# LR-CR.net
KiCad netlist of a schematic drawn in EAGLE
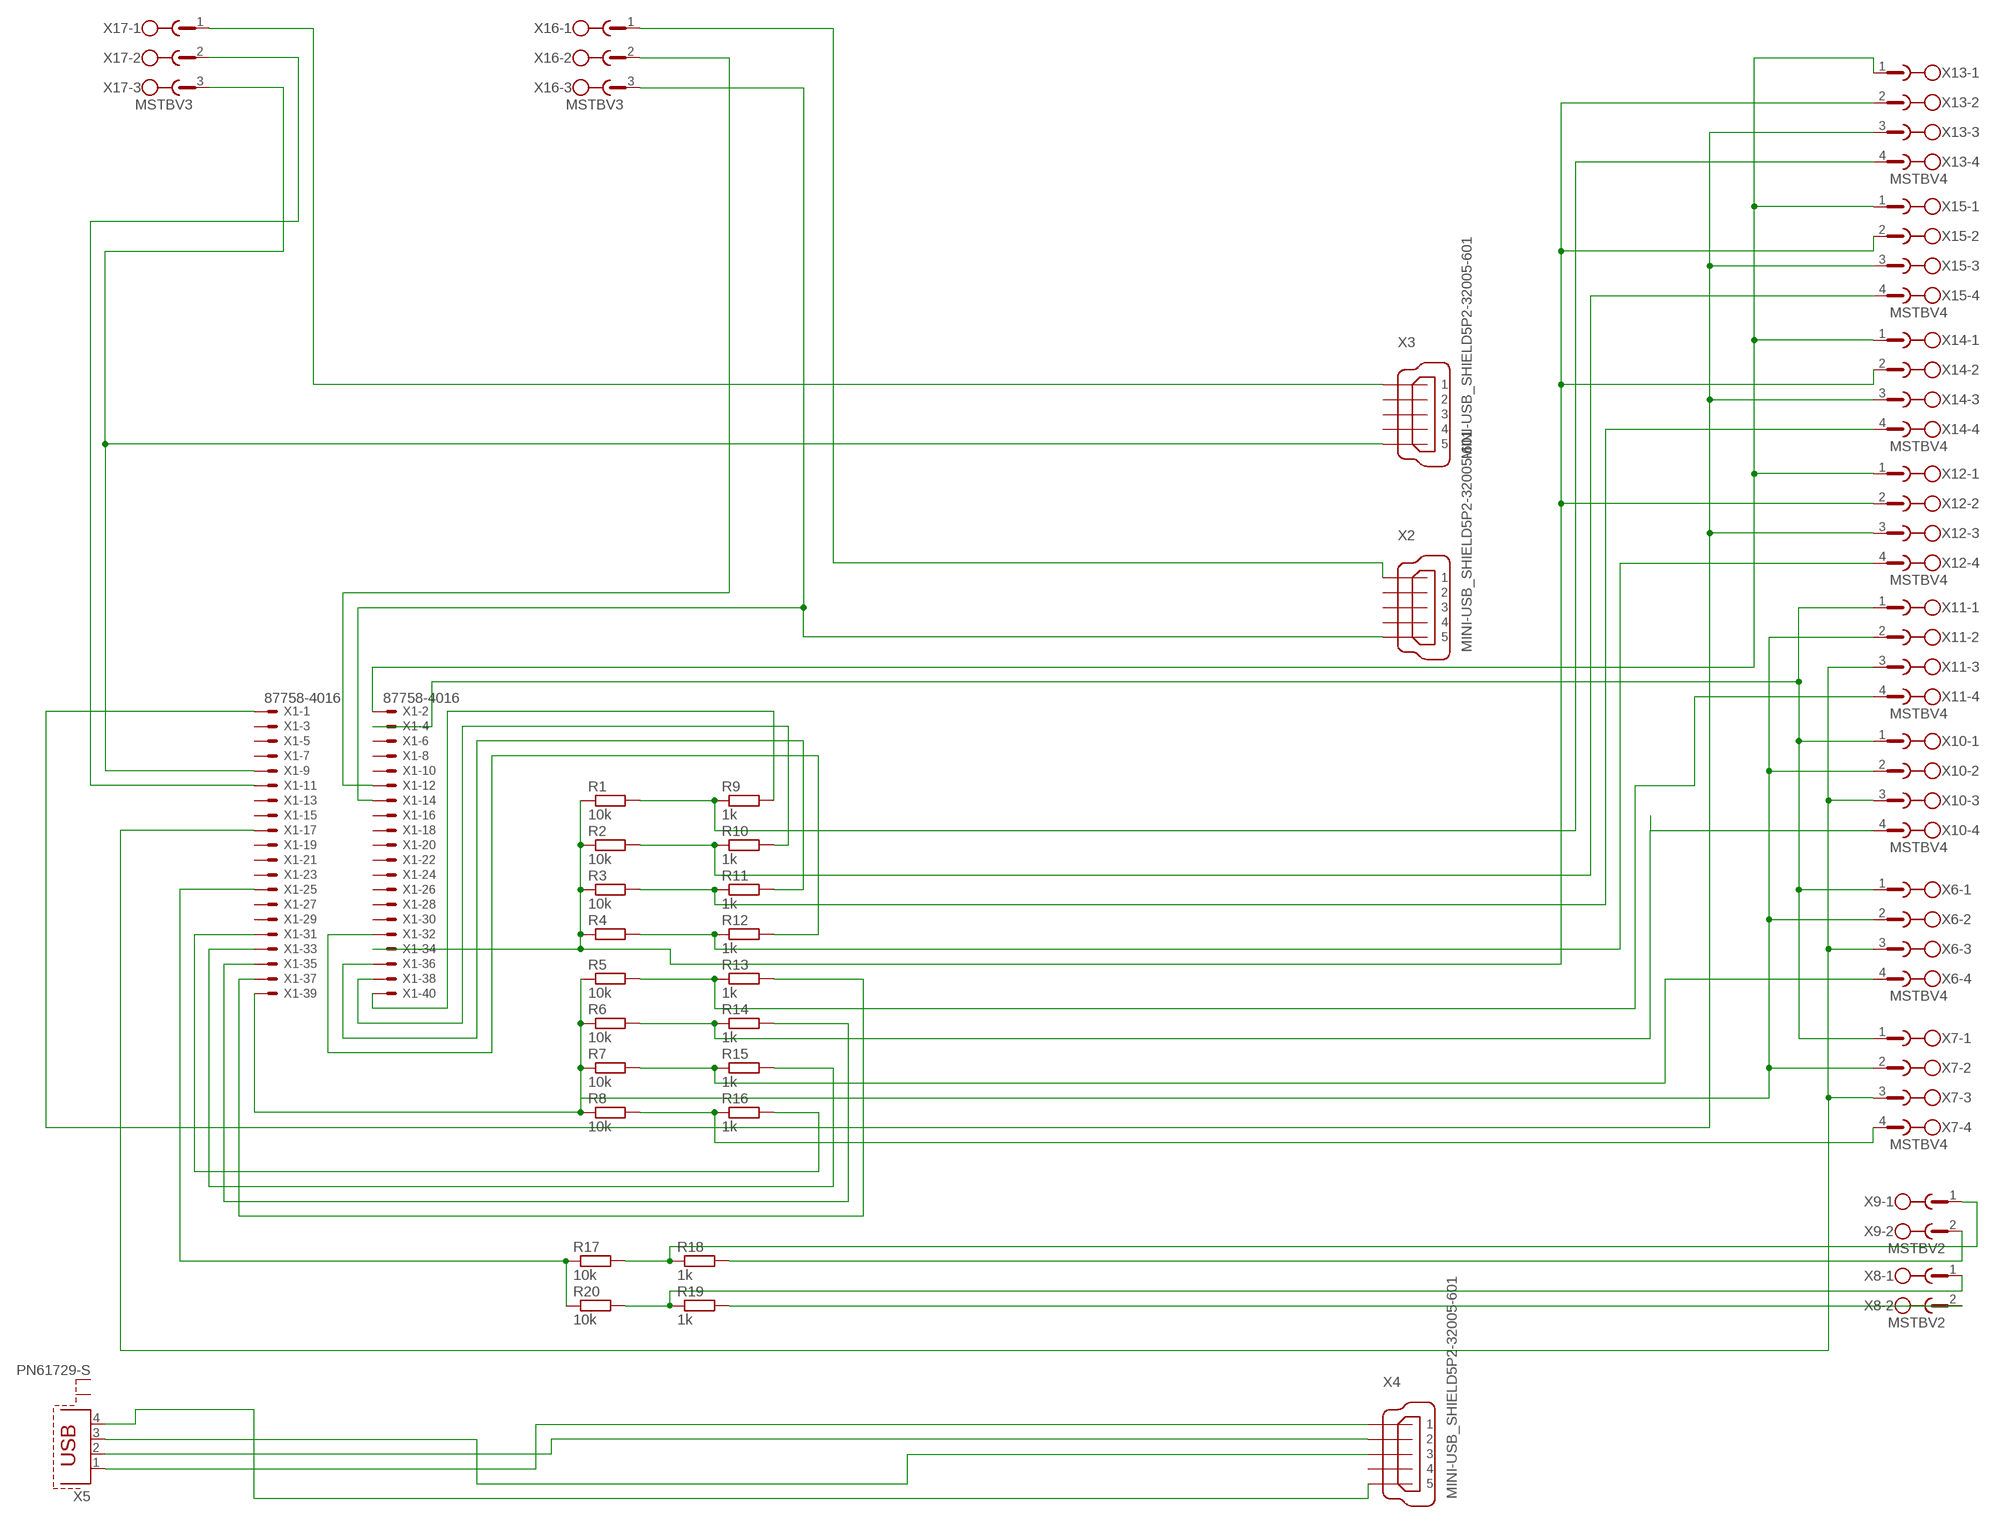
[diagram p0: schematic, sheet 1]

(export (version "E")
  (design (tool "Eeschema 10.0.6"))
  (components
    (comp (ref "R1")
      (value "10k")
      (footprint "eagle-import:0411_15")
      (libsource (lib "eagle-import") (part "R-EU_0411/15"))
    )
    (comp (ref "R2")
      (value "10k")
      (footprint "eagle-import:0411_15")
      (libsource (lib "eagle-import") (part "R-EU_0411/15"))
    )
    (comp (ref "R3")
      (value "10k")
      (footprint "eagle-import:0411_15")
      (libsource (lib "eagle-import") (part "R-EU_0411/15"))
    )
    (comp (ref "R4")
      (value "R-EU_0411/15")
      (footprint "eagle-import:0411_15")
      (libsource (lib "eagle-import") (part "R-EU_0411/15"))
    )
    (comp (ref "R5")
      (value "10k")
      (footprint "eagle-import:0411_15")
      (libsource (lib "eagle-import") (part "R-EU_0411/15"))
    )
    (comp (ref "R6")
      (value "10k")
      (footprint "eagle-import:0411_15")
      (libsource (lib "eagle-import") (part "R-EU_0411/15"))
    )
    (comp (ref "R7")
      (value "10k")
      (footprint "eagle-import:0411_15")
      (libsource (lib "eagle-import") (part "R-EU_0411/15"))
    )
    (comp (ref "R8")
      (value "10k")
      (footprint "eagle-import:0411_15")
      (libsource (lib "eagle-import") (part "R-EU_0411/15"))
    )
    (comp (ref "R9")
      (value "1k")
      (footprint "eagle-import:0411_15")
      (libsource (lib "eagle-import") (part "R-EU_0411/15"))
    )
    (comp (ref "R10")
      (value "1k")
      (footprint "eagle-import:0411_15")
      (libsource (lib "eagle-import") (part "R-EU_0411/15"))
    )
    (comp (ref "R11")
      (value "1k")
      (footprint "eagle-import:0411_15")
      (libsource (lib "eagle-import") (part "R-EU_0411/15"))
    )
    (comp (ref "R12")
      (value "1k")
      (footprint "eagle-import:0411_15")
      (libsource (lib "eagle-import") (part "R-EU_0411/15"))
    )
    (comp (ref "R13")
      (value "1k")
      (footprint "eagle-import:0411_15")
      (libsource (lib "eagle-import") (part "R-EU_0411/15"))
    )
    (comp (ref "R14")
      (value "1k")
      (footprint "eagle-import:0411_15")
      (libsource (lib "eagle-import") (part "R-EU_0411/15"))
    )
    (comp (ref "R15")
      (value "1k")
      (footprint "eagle-import:0411_15")
      (libsource (lib "eagle-import") (part "R-EU_0411/15"))
    )
    (comp (ref "R16")
      (value "1k")
      (footprint "eagle-import:0411_15")
      (libsource (lib "eagle-import") (part "R-EU_0411/15"))
    )
    (comp (ref "R17")
      (value "10k")
      (footprint "eagle-import:0411_15")
      (libsource (lib "eagle-import") (part "R-EU_0411/15"))
    )
    (comp (ref "R18")
      (value "1k")
      (footprint "eagle-import:0411_15")
      (libsource (lib "eagle-import") (part "R-EU_0411/15"))
    )
    (comp (ref "R19")
      (value "1k")
      (footprint "eagle-import:0411_15")
      (libsource (lib "eagle-import") (part "R-EU_0411/15"))
    )
    (comp (ref "R20")
      (value "10k")
      (footprint "eagle-import:0411_15")
      (libsource (lib "eagle-import") (part "R-EU_0411/15"))
    )
    (comp (ref "X1")
      (value "87758-4016")
      (footprint "eagle-import:87758-4016")
      (fields (field (name "MF") "MOLEX"))
      (libsource (lib "eagle-import") (part "87758-4016"))
    )
    (comp (ref "X2")
      (value "MINI-USB_SHIELD5P2-32005-601")
      (footprint "eagle-import:32005-601")
      (libsource (lib "eagle-import") (part "MINI-USB_SHIELD5P2-32005-601"))
    )
    (comp (ref "X3")
      (value "MINI-USB_SHIELD5P2-32005-601")
      (footprint "eagle-import:32005-601")
      (libsource (lib "eagle-import") (part "MINI-USB_SHIELD5P2-32005-601"))
    )
    (comp (ref "X4")
      (value "MINI-USB_SHIELD5P2-32005-601")
      (footprint "eagle-import:32005-601")
      (libsource (lib "eagle-import") (part "MINI-USB_SHIELD5P2-32005-601"))
    )
    (comp (ref "X5")
      (value "PN61729-S")
      (footprint "eagle-import:PN61729-S")
      (libsource (lib "eagle-import") (part "PN61729-S"))
    )
    (comp (ref "X6")
      (value "MSTBV4")
      (footprint "eagle-import:MSTBV4")
      (fields (field (name "MPN") "MSTBV 2,5/4-GF-5.08"))
      (libsource (lib "eagle-import") (part "MSTBV4"))
    )
    (comp (ref "X7")
      (value "MSTBV4")
      (footprint "eagle-import:MSTBV4")
      (fields (field (name "MPN") "MSTBV 2,5/4-GF-5.08"))
      (libsource (lib "eagle-import") (part "MSTBV4"))
    )
    (comp (ref "X8")
      (value "MSTBV2")
      (footprint "eagle-import:MSTBV2")
      (fields (field (name "MPN") "MSTBV 2,5/2-GF-5.08"))
      (libsource (lib "eagle-import") (part "MSTBV2"))
    )
    (comp (ref "X9")
      (value "MSTBV2")
      (footprint "eagle-import:MSTBV2")
      (fields (field (name "MPN") "MSTBV 2,5/2-GF-5.08"))
      (libsource (lib "eagle-import") (part "MSTBV2"))
    )
    (comp (ref "X10")
      (value "MSTBV4")
      (footprint "eagle-import:MSTBV4")
      (fields (field (name "MPN") "MSTBV 2,5/4-GF-5.08"))
      (libsource (lib "eagle-import") (part "MSTBV4"))
    )
    (comp (ref "X11")
      (value "MSTBV4")
      (footprint "eagle-import:MSTBV4")
      (fields (field (name "MPN") "MSTBV 2,5/4-GF-5.08"))
      (libsource (lib "eagle-import") (part "MSTBV4"))
    )
    (comp (ref "X12")
      (value "MSTBV4")
      (footprint "eagle-import:MSTBV4")
      (fields (field (name "MPN") "MSTBV 2,5/4-GF-5.08"))
      (libsource (lib "eagle-import") (part "MSTBV4"))
    )
    (comp (ref "X13")
      (value "MSTBV4")
      (footprint "eagle-import:MSTBV4")
      (fields (field (name "MPN") "MSTBV 2,5/4-GF-5.08"))
      (libsource (lib "eagle-import") (part "MSTBV4"))
    )
    (comp (ref "X14")
      (value "MSTBV4")
      (footprint "eagle-import:MSTBV4")
      (fields (field (name "MPN") "MSTBV 2,5/4-GF-5.08"))
      (libsource (lib "eagle-import") (part "MSTBV4"))
    )
    (comp (ref "X15")
      (value "MSTBV4")
      (footprint "eagle-import:MSTBV4")
      (fields (field (name "MPN") "MSTBV 2,5/4-GF-5.08"))
      (libsource (lib "eagle-import") (part "MSTBV4"))
    )
    (comp (ref "X16")
      (value "MSTBV3")
      (footprint "eagle-import:MSTBV3")
      (fields (field (name "MPN") "MSTBV 2,5/3-GF-5.08"))
      (libsource (lib "eagle-import") (part "MSTBV3"))
    )
    (comp (ref "X17")
      (value "MSTBV3")
      (footprint "eagle-import:MSTBV3")
      (fields (field (name "MPN") "MSTBV 2,5/3-GF-5.08"))
      (libsource (lib "eagle-import") (part "MSTBV3"))
    )
  )
  (nets
    (net (code "1") (name "Net-(R17-Pad2)") (class "Default")
      (node (ref "R17") (pin "2") (pinfunction "2_2") (pintype "passive"))
      (node (ref "R18") (pin "1") (pinfunction "1_1") (pintype "passive"))
      (node (ref "X9") (pin "1") (pinfunction "1_1") (pintype "passive"))
    )
    (net (code "2") (name "Net-(R19-Pad1)") (class "Default")
      (node (ref "R19") (pin "1") (pinfunction "1_1") (pintype "passive"))
      (node (ref "R20") (pin "2") (pinfunction "2_2") (pintype "passive"))
      (node (ref "X8") (pin "1") (pinfunction "1_1") (pintype "passive"))
    )
    (net (code "3") (name "Net-(X1AA-S)") (class "Default")
      (node (ref "R15") (pin "2") (pinfunction "2_2") (pintype "passive"))
      (node (ref "X1") (pin "33") (pinfunction "S_33") (pintype "passive"))
    )
    (net (code "4") (name "Net-(X1AC-S)") (class "Default")
      (node (ref "R14") (pin "2") (pinfunction "2_2") (pintype "passive"))
      (node (ref "X1") (pin "35") (pinfunction "S_35") (pintype "passive"))
    )
    (net (code "5") (name "Net-(X1AD-S)") (class "Default")
      (node (ref "R11") (pin "2") (pinfunction "2_2") (pintype "passive"))
      (node (ref "X1") (pin "36") (pinfunction "S_36") (pintype "passive"))
    )
    (net (code "6") (name "Net-(X1AE-S)") (class "Default")
      (node (ref "R13") (pin "2") (pinfunction "2_2") (pintype "passive"))
      (node (ref "X1") (pin "37") (pinfunction "S_37") (pintype "passive"))
    )
    (net (code "7") (name "Net-(X1AF-S)") (class "Default")
      (node (ref "R10") (pin "2") (pinfunction "2_2") (pintype "passive"))
      (node (ref "X1") (pin "38") (pinfunction "S_38") (pintype "passive"))
    )
    (net (code "8") (name "Net-(X1AH-S)") (class "Default")
      (node (ref "X1") (pin "4") (pinfunction "S_4") (pintype "passive"))
      (node (ref "X10") (pin "1") (pinfunction "1_1") (pintype "passive"))
      (node (ref "X11") (pin "1") (pinfunction "1_1") (pintype "passive"))
      (node (ref "X6") (pin "1") (pinfunction "1_1") (pintype "passive"))
      (node (ref "X7") (pin "1") (pinfunction "1_1") (pintype "passive"))
    )
    (net (code "9") (name "Net-(X1AI-S)") (class "Default")
      (node (ref "R9") (pin "2") (pinfunction "2_2") (pintype "passive"))
      (node (ref "X1") (pin "40") (pinfunction "S_40") (pintype "passive"))
    )
    (net (code "10") (name "Net-(X1L-S)") (class "Default")
      (node (ref "X1") (pin "2") (pinfunction "S_2") (pintype "passive"))
      (node (ref "X12") (pin "1") (pinfunction "1_1") (pintype "passive"))
      (node (ref "X13") (pin "1") (pinfunction "1_1") (pintype "passive"))
      (node (ref "X14") (pin "1") (pinfunction "1_1") (pintype "passive"))
      (node (ref "X15") (pin "1") (pinfunction "1_1") (pintype "passive"))
    )
    (net (code "11") (name "Net-(X1R-S)") (class "Default")
      (node (ref "R17") (pin "1") (pinfunction "1_1") (pintype "passive"))
      (node (ref "R20") (pin "1") (pinfunction "1_1") (pintype "passive"))
      (node (ref "X1") (pin "25") (pinfunction "S_25") (pintype "passive"))
    )
    (net (code "12") (name "Net-(X1Y-S)") (class "Default")
      (node (ref "R16") (pin "2") (pinfunction "2_2") (pintype "passive"))
      (node (ref "X1") (pin "31") (pinfunction "S_31") (pintype "passive"))
    )
    (net (code "13") (name "Net-(X1Z-S)") (class "Default")
      (node (ref "R12") (pin "2") (pinfunction "2_2") (pintype "passive"))
      (node (ref "X1") (pin "32") (pinfunction "S_32") (pintype "passive"))
    )
    (net (code "14") (name "Net-(X4-Pad1)") (class "Default")
      (node (ref "X4") (pin "1") (pinfunction "1_1") (pintype "passive"))
      (node (ref "X5") (pin "1") (pinfunction "1_1") (pintype "passive"))
    )
    (net (code "15") (name "Net-(X4-Pad2)") (class "Default")
      (node (ref "X4") (pin "2") (pinfunction "2_2") (pintype "passive"))
      (node (ref "X5") (pin "2") (pinfunction "2_2") (pintype "passive"))
    )
    (net (code "16") (name "Net-(X4-Pad3)") (class "Default")
      (node (ref "X4") (pin "3") (pinfunction "3_3") (pintype "passive"))
      (node (ref "X5") (pin "3") (pinfunction "3_3") (pintype "passive"))
    )
    (net (code "17") (name "Net-(X4-Pad5)") (class "Default")
      (node (ref "X4") (pin "5") (pinfunction "5_5") (pintype "passive"))
      (node (ref "X5") (pin "4") (pinfunction "4_4") (pintype "passive"))
    )
    (net (code "18") (name "Net-(X6D-1)") (class "Default")
      (node (ref "R15") (pin "1") (pinfunction "1_1") (pintype "passive"))
      (node (ref "R7") (pin "2") (pinfunction "2_2") (pintype "passive"))
      (node (ref "X6") (pin "4") (pinfunction "1_4") (pintype "passive"))
    )
    (net (code "19") (name "Net-(X7D-1)") (class "Default")
      (node (ref "R16") (pin "1") (pinfunction "1_1") (pintype "passive"))
      (node (ref "R8") (pin "2") (pinfunction "2_2") (pintype "passive"))
      (node (ref "X7") (pin "4") (pinfunction "1_4") (pintype "passive"))
    )
    (net (code "20") (name "Net-(X8B-1)") (class "Default")
      (node (ref "R19") (pin "2") (pinfunction "2_2") (pintype "passive"))
      (node (ref "X8") (pin "2") (pinfunction "1_2") (pintype "passive"))
    )
    (net (code "21") (name "Net-(X9B-1)") (class "Default")
      (node (ref "R18") (pin "2") (pinfunction "2_2") (pintype "passive"))
      (node (ref "X9") (pin "2") (pinfunction "1_2") (pintype "passive"))
    )
    (net (code "22") (name "Net-(X10B-1)") (class "Default")
      (node (ref "R5") (pin "1") (pinfunction "1_1") (pintype "passive"))
      (node (ref "R6") (pin "1") (pinfunction "1_1") (pintype "passive"))
      (node (ref "R7") (pin "1") (pinfunction "1_1") (pintype "passive"))
      (node (ref "R8") (pin "1") (pinfunction "1_1") (pintype "passive"))
      (node (ref "X1") (pin "39") (pinfunction "S_39") (pintype "passive"))
      (node (ref "X10") (pin "2") (pinfunction "1_2") (pintype "passive"))
      (node (ref "X11") (pin "2") (pinfunction "1_2") (pintype "passive"))
      (node (ref "X6") (pin "2") (pinfunction "1_2") (pintype "passive"))
      (node (ref "X7") (pin "2") (pinfunction "1_2") (pintype "passive"))
    )
    (net (code "23") (name "Net-(X10C-1)") (class "Default")
      (node (ref "X1") (pin "17") (pinfunction "S_17") (pintype "passive"))
      (node (ref "X10") (pin "3") (pinfunction "1_3") (pintype "passive"))
      (node (ref "X11") (pin "3") (pinfunction "1_3") (pintype "passive"))
      (node (ref "X6") (pin "3") (pinfunction "1_3") (pintype "passive"))
      (node (ref "X7") (pin "3") (pinfunction "1_3") (pintype "passive"))
    )
    (net (code "24") (name "Net-(X10D-1)") (class "Default")
      (node (ref "R14") (pin "1") (pinfunction "1_1") (pintype "passive"))
      (node (ref "R6") (pin "2") (pinfunction "2_2") (pintype "passive"))
      (node (ref "X10") (pin "4") (pinfunction "1_4") (pintype "passive"))
    )
    (net (code "25") (name "Net-(X11D-1)") (class "Default")
      (node (ref "R13") (pin "1") (pinfunction "1_1") (pintype "passive"))
      (node (ref "R5") (pin "2") (pinfunction "2_2") (pintype "passive"))
      (node (ref "X11") (pin "4") (pinfunction "1_4") (pintype "passive"))
    )
    (net (code "26") (name "Net-(X12B-1)") (class "Default")
      (node (ref "R1") (pin "1") (pinfunction "1_1") (pintype "passive"))
      (node (ref "R2") (pin "1") (pinfunction "1_1") (pintype "passive"))
      (node (ref "R3") (pin "1") (pinfunction "1_1") (pintype "passive"))
      (node (ref "R4") (pin "1") (pinfunction "1_1") (pintype "passive"))
      (node (ref "X1") (pin "34") (pinfunction "S_34") (pintype "passive"))
      (node (ref "X12") (pin "2") (pinfunction "1_2") (pintype "passive"))
      (node (ref "X13") (pin "2") (pinfunction "1_2") (pintype "passive"))
      (node (ref "X14") (pin "2") (pinfunction "1_2") (pintype "passive"))
      (node (ref "X15") (pin "2") (pinfunction "1_2") (pintype "passive"))
    )
    (net (code "27") (name "Net-(X12C-1)") (class "Default")
      (node (ref "X1") (pin "1") (pinfunction "S_1") (pintype "passive"))
      (node (ref "X12") (pin "3") (pinfunction "1_3") (pintype "passive"))
      (node (ref "X13") (pin "3") (pinfunction "1_3") (pintype "passive"))
      (node (ref "X14") (pin "3") (pinfunction "1_3") (pintype "passive"))
      (node (ref "X15") (pin "3") (pinfunction "1_3") (pintype "passive"))
    )
    (net (code "28") (name "Net-(X12D-1)") (class "Default")
      (node (ref "R12") (pin "1") (pinfunction "1_1") (pintype "passive"))
      (node (ref "R4") (pin "2") (pinfunction "2_2") (pintype "passive"))
      (node (ref "X12") (pin "4") (pinfunction "1_4") (pintype "passive"))
    )
    (net (code "29") (name "Net-(X13D-1)") (class "Default")
      (node (ref "R1") (pin "2") (pinfunction "2_2") (pintype "passive"))
      (node (ref "R9") (pin "1") (pinfunction "1_1") (pintype "passive"))
      (node (ref "X13") (pin "4") (pinfunction "1_4") (pintype "passive"))
    )
    (net (code "30") (name "Net-(X14D-1)") (class "Default")
      (node (ref "R11") (pin "1") (pinfunction "1_1") (pintype "passive"))
      (node (ref "R3") (pin "2") (pinfunction "2_2") (pintype "passive"))
      (node (ref "X14") (pin "4") (pinfunction "1_4") (pintype "passive"))
    )
    (net (code "31") (name "Net-(X15D-1)") (class "Default")
      (node (ref "R10") (pin "1") (pinfunction "1_1") (pintype "passive"))
      (node (ref "R2") (pin "2") (pinfunction "2_2") (pintype "passive"))
      (node (ref "X15") (pin "4") (pinfunction "1_4") (pintype "passive"))
    )
    (net (code "32") (name "Net-(X16-Pad1)") (class "Default")
      (node (ref "X16") (pin "1") (pinfunction "1_1") (pintype "passive"))
      (node (ref "X2") (pin "1") (pinfunction "1_1") (pintype "passive"))
    )
    (net (code "33") (name "Net-(X16B-1)") (class "Default")
      (node (ref "X1") (pin "12") (pinfunction "S_12") (pintype "passive"))
      (node (ref "X16") (pin "2") (pinfunction "1_2") (pintype "passive"))
    )
    (net (code "34") (name "Net-(X16C-1)") (class "Default")
      (node (ref "X1") (pin "14") (pinfunction "S_14") (pintype "passive"))
      (node (ref "X16") (pin "3") (pinfunction "1_3") (pintype "passive"))
      (node (ref "X2") (pin "5") (pinfunction "5_5") (pintype "passive"))
    )
    (net (code "35") (name "Net-(X17-Pad1)") (class "Default")
      (node (ref "X17") (pin "1") (pinfunction "1_1") (pintype "passive"))
      (node (ref "X3") (pin "1") (pinfunction "1_1") (pintype "passive"))
    )
    (net (code "36") (name "Net-(X17B-1)") (class "Default")
      (node (ref "X1") (pin "11") (pinfunction "S_11") (pintype "passive"))
      (node (ref "X17") (pin "2") (pinfunction "1_2") (pintype "passive"))
    )
    (net (code "37") (name "Net-(X17C-1)") (class "Default")
      (node (ref "X1") (pin "9") (pinfunction "S_9") (pintype "passive"))
      (node (ref "X17") (pin "3") (pinfunction "1_3") (pintype "passive"))
      (node (ref "X3") (pin "5") (pinfunction "5_5") (pintype "passive"))
    )
    (net (code "38") (name "unconnected-(X1AJ-S-Pad5)") (class "Default")
      (node (ref "X1") (pin "5") (pinfunction "S_5") (pintype "passive"))
    )
    (net (code "39") (name "unconnected-(X1AK-S-Pad6)") (class "Default")
      (node (ref "X1") (pin "6") (pinfunction "S_6") (pintype "passive"))
    )
    (net (code "40") (name "unconnected-(X1AL-S-Pad7)") (class "Default")
      (node (ref "X1") (pin "7") (pinfunction "S_7") (pintype "passive"))
    )
    (net (code "41") (name "unconnected-(X1AM-S-Pad8)") (class "Default")
      (node (ref "X1") (pin "8") (pinfunction "S_8") (pintype "passive"))
    )
    (net (code "42") (name "unconnected-(X1B-S-Pad10)") (class "Default")
      (node (ref "X1") (pin "10") (pinfunction "S_10") (pintype "passive"))
    )
    (net (code "43") (name "unconnected-(X1E-S-Pad13)") (class "Default")
      (node (ref "X1") (pin "13") (pinfunction "S_13") (pintype "passive"))
    )
    (net (code "44") (name "unconnected-(X1G-S-Pad15)") (class "Default")
      (node (ref "X1") (pin "15") (pinfunction "S_15") (pintype "passive"))
    )
    (net (code "45") (name "unconnected-(X1H-S-Pad16)") (class "Default")
      (node (ref "X1") (pin "16") (pinfunction "S_16") (pintype "passive"))
    )
    (net (code "46") (name "unconnected-(X1J-S-Pad18)") (class "Default")
      (node (ref "X1") (pin "18") (pinfunction "S_18") (pintype "passive"))
    )
    (net (code "47") (name "unconnected-(X1K-S-Pad19)") (class "Default")
      (node (ref "X1") (pin "19") (pinfunction "S_19") (pintype "passive"))
    )
    (net (code "48") (name "unconnected-(X1M-S-Pad20)") (class "Default")
      (node (ref "X1") (pin "20") (pinfunction "S_20") (pintype "passive"))
    )
    (net (code "49") (name "unconnected-(X1N-S-Pad21)") (class "Default")
      (node (ref "X1") (pin "21") (pinfunction "S_21") (pintype "passive"))
    )
    (net (code "50") (name "unconnected-(X1O-S-Pad22)") (class "Default")
      (node (ref "X1") (pin "22") (pinfunction "S_22") (pintype "passive"))
    )
    (net (code "51") (name "unconnected-(X1P-S-Pad23)") (class "Default")
      (node (ref "X1") (pin "23") (pinfunction "S_23") (pintype "passive"))
    )
    (net (code "52") (name "unconnected-(X1Q-S-Pad24)") (class "Default")
      (node (ref "X1") (pin "24") (pinfunction "S_24") (pintype "passive"))
    )
    (net (code "53") (name "unconnected-(X1S-S-Pad26)") (class "Default")
      (node (ref "X1") (pin "26") (pinfunction "S_26") (pintype "passive"))
    )
    (net (code "54") (name "unconnected-(X1T-S-Pad27)") (class "Default")
      (node (ref "X1") (pin "27") (pinfunction "S_27") (pintype "passive"))
    )
    (net (code "55") (name "unconnected-(X1U-S-Pad28)") (class "Default")
      (node (ref "X1") (pin "28") (pinfunction "S_28") (pintype "passive"))
    )
    (net (code "56") (name "unconnected-(X1V-S-Pad29)") (class "Default")
      (node (ref "X1") (pin "29") (pinfunction "S_29") (pintype "passive"))
    )
    (net (code "57") (name "unconnected-(X1W-S-Pad3)") (class "Default")
      (node (ref "X1") (pin "3") (pinfunction "S_3") (pintype "passive"))
    )
    (net (code "58") (name "unconnected-(X1X-S-Pad30)") (class "Default")
      (node (ref "X1") (pin "30") (pinfunction "S_30") (pintype "passive"))
    )
    (net (code "59") (name "unconnected-(X2-Pad2)") (class "Default")
      (node (ref "X2") (pin "2") (pinfunction "2_2") (pintype "passive"))
    )
    (net (code "60") (name "unconnected-(X2-Pad3)") (class "Default")
      (node (ref "X2") (pin "3") (pinfunction "3_3") (pintype "passive"))
    )
    (net (code "61") (name "unconnected-(X2-Pad4)") (class "Default")
      (node (ref "X2") (pin "4") (pinfunction "4_4") (pintype "passive"))
    )
    (net (code "62") (name "unconnected-(X3-Pad2)") (class "Default")
      (node (ref "X3") (pin "2") (pinfunction "2_2") (pintype "passive"))
    )
    (net (code "63") (name "unconnected-(X3-Pad3)") (class "Default")
      (node (ref "X3") (pin "3") (pinfunction "3_3") (pintype "passive"))
    )
    (net (code "64") (name "unconnected-(X3-Pad4)") (class "Default")
      (node (ref "X3") (pin "4") (pinfunction "4_4") (pintype "passive"))
    )
    (net (code "65") (name "unconnected-(X4-Pad4)") (class "Default")
      (node (ref "X4") (pin "4") (pinfunction "4_4") (pintype "passive"))
    )
    (net (code "66") (name "unconnected-(X5-PadS1)") (class "Default")
      (node (ref "X5") (pin "S1") (pinfunction "S1_S1") (pintype "passive"))
    )
    (net (code "67") (name "unconnected-(X5-PadS2)") (class "Default")
      (node (ref "X5") (pin "S2") (pinfunction "S2_S2") (pintype "passive"))
    )
  )
)
